# Cell_Monitor_V0_1.net
KiCad netlist of a schematic drawn in Altium Designer
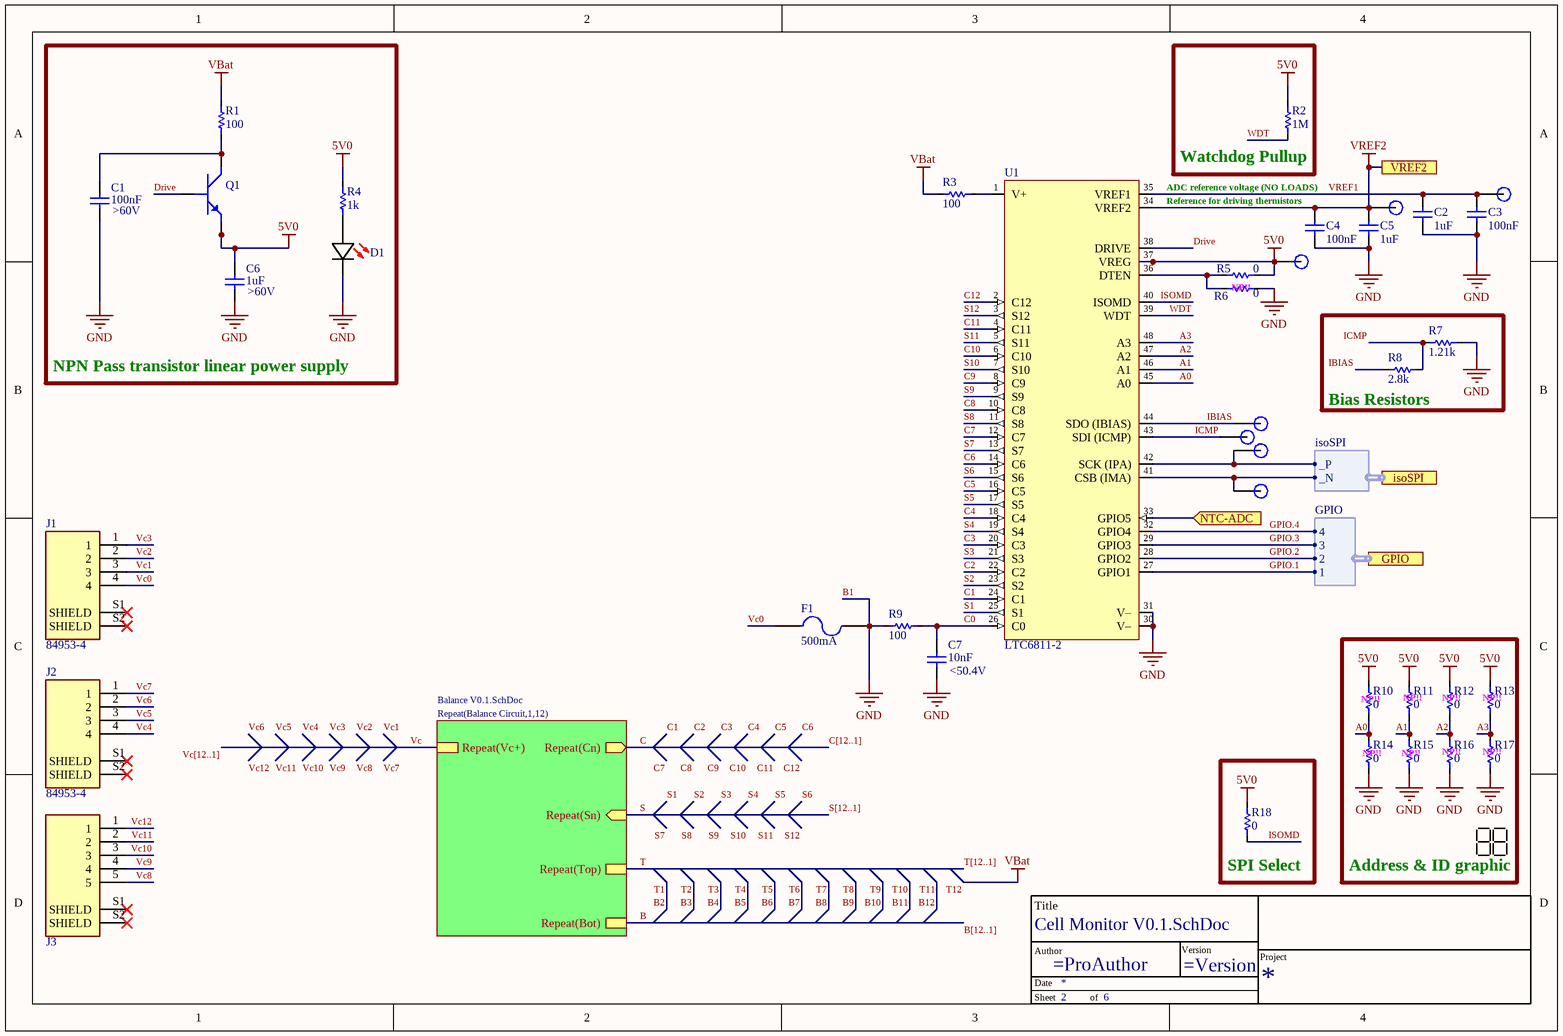
[diagram p0: Cell Monitor V0.1.SchDoc]

(export (version "E")
  (design (tool "Eeschema 10.0.6"))
  (components
    (comp (ref "*") (value "TitleBlock") (libsource (lib "SchematicLib") (part "TitleBlock")))
    (comp (ref "C1")
      (value "100nF")
      (footprint "C_0603")
      (description "Capacitor")
      (fields (field (name "VOLTAGE") ">60V") (field (name "Comment") "C"))
      (libsource (lib "Passives") (part "Capacitor"))
    )
    (comp (ref "C2")
      (value "1uF")
      (footprint "C-0402")
      (description "Capacitor")
      (fields (field (name "Comment") "C"))
      (libsource (lib "Passives") (part "Capacitor"))
    )
    (comp (ref "C3")
      (value "100nF")
      (footprint "C-0402")
      (description "Capacitor")
      (fields (field (name "Comment") "C"))
      (libsource (lib "Passives") (part "Capacitor"))
    )
    (comp (ref "C4")
      (value "100nF")
      (footprint "C-0402")
      (description "Capacitor")
      (fields (field (name "Comment") "C"))
      (libsource (lib "Passives") (part "Capacitor"))
    )
    (comp (ref "C5")
      (value "1uF")
      (footprint "C-0402")
      (description "Capacitor")
      (fields (field (name "Comment") "C"))
      (libsource (lib "Passives") (part "Capacitor"))
    )
    (comp (ref "C6")
      (value "1uF")
      (footprint "C_0603")
      (description "Capacitor")
      (fields (field (name "VOLTAGE") ">60V") (field (name "Comment") "C"))
      (libsource (lib "Passives") (part "Capacitor"))
    )
    (comp (ref "C7")
      (value "10nF")
      (footprint "C_0603")
      (description "Capacitor")
      (fields (field (name "VOLTAGE") "<50.4V") (field (name "Comment") "C"))
      (libsource (lib "Passives") (part "Capacitor"))
    )
    (comp (ref "D1")
      (value "150060SS55040")
      (footprint "LED (0603)")
      (description "LED RED DIFFUSED 0603 SMD")
      (fields (field (name "MANUFACTURER") "Wurth Electronics"))
      (libsource (lib "LEDLib") (part "150060SS55040"))
    )
    (comp (ref "F1")
      (value "0466.500NR")
      (footprint "0466.500NR")
      (fields
        (field (name "MANUFACTURER") "Littelfuse")
        (field (name "CURRENT RATING") "500mA")
        (field (name "PUBLISHER") "Altium Limited")
      )
      (libsource (lib "Miscellaneous Devices") (part "Fuse 2"))
    )
    (comp (ref "J1")
      (value "84953-4")
      (footprint "84953-4")
      (fields (field (name "MF") "{'manufacturer': u'TE Connectivity'}"))
      (libsource (lib "TE_Con") (part "84953-4"))
    )
    (comp (ref "J2")
      (value "84953-4")
      (footprint "84953-4")
      (fields (field (name "MF") "{'manufacturer': u'TE Connectivity'}"))
      (libsource (lib "TE_Con") (part "84953-4"))
    )
    (comp (ref "J3") (value "84953-5") (footprint "84953-5") (libsource (lib "TE_Con") (part "84953-5")))
    (comp (ref "NT1") (value "NetTie") (footprint "NetTie") (libsource (lib "SchematicLib") (part "NetTie")))
    (comp (ref "NT2") (value "NetTie") (footprint "NetTie") (libsource (lib "SchematicLib") (part "NetTie")))
    (comp (ref "Q1")
      (value "PHPT60603NYX")
      (footprint "LFPAK56 (SOT669)")
      (description "60V, 3 A NPN high power bipolar transistor")
      (libsource (lib "SchematicLib") (part "PHPT60603NYX"))
    )
    (comp (ref "R1")
      (value "100")
      (footprint "R_2010")
      (description "Resistor")
      (libsource (lib "Passives") (part "Resistor"))
    )
    (comp (ref "R2")
      (value "1M")
      (footprint "R_0402")
      (description "Resistor")
      (libsource (lib "Passives") (part "Resistor"))
    )
    (comp (ref "R3")
      (value "100")
      (footprint "R_2010")
      (description "Resistor")
      (libsource (lib "Passives") (part "Resistor"))
    )
    (comp (ref "R4")
      (value "1k")
      (footprint "R-0603")
      (description "Resistor")
      (libsource (lib "Passives") (part "Resistor"))
    )
    (comp (ref "R5")
      (value "0")
      (footprint "R_0402")
      (description "Resistor")
      (libsource (lib "Passives") (part "Resistor"))
    )
    (comp (ref "R6")
      (value "0")
      (footprint "R_0402")
      (description "Resistor")
      (libsource (lib "Passives") (part "Resistor"))
    )
    (comp (ref "R7")
      (value "1.21k")
      (footprint "R_0402")
      (description "Resistor")
      (libsource (lib "Passives") (part "Resistor"))
    )
    (comp (ref "R8")
      (value "2.8k")
      (footprint "R_0402")
      (description "Resistor")
      (libsource (lib "Passives") (part "Resistor"))
    )
    (comp (ref "R9")
      (value "100")
      (footprint "R-0603")
      (description "Resistor")
      (libsource (lib "Passives") (part "Resistor"))
    )
    (comp (ref "R10")
      (value "0")
      (footprint "R_0402")
      (description "Resistor")
      (libsource (lib "Passives") (part "Resistor"))
    )
    (comp (ref "R11")
      (value "0")
      (footprint "R_0402")
      (description "Resistor")
      (libsource (lib "Passives") (part "Resistor"))
    )
    (comp (ref "R12")
      (value "0")
      (footprint "R_0402")
      (description "Resistor")
      (libsource (lib "Passives") (part "Resistor"))
    )
    (comp (ref "R13")
      (value "0")
      (footprint "R_0402")
      (description "Resistor")
      (libsource (lib "Passives") (part "Resistor"))
    )
    (comp (ref "R14")
      (value "0")
      (footprint "R_0402")
      (description "Resistor")
      (libsource (lib "Passives") (part "Resistor"))
    )
    (comp (ref "R15")
      (value "0")
      (footprint "R_0402")
      (description "Resistor")
      (libsource (lib "Passives") (part "Resistor"))
    )
    (comp (ref "R16")
      (value "0")
      (footprint "R_0402")
      (description "Resistor")
      (libsource (lib "Passives") (part "Resistor"))
    )
    (comp (ref "R17")
      (value "0")
      (footprint "R_0402")
      (description "Resistor")
      (libsource (lib "Passives") (part "Resistor"))
    )
    (comp (ref "R18")
      (value "0")
      (footprint "R_0402")
      (description "Resistor")
      (libsource (lib "Passives") (part "Resistor"))
    )
    (comp (ref "S1")
      (value "2x7Segment")
      (footprint "2x7Segment")
      (libsource (lib "SchematicLib") (part "2x7Segment"))
    )
    (comp (ref "TP1")
      (value "VREF1")
      (footprint "Test Point")
      (description "1.2mm Test point")
      (libsource (lib "SchematicLib") (part "Test Point"))
    )
    (comp (ref "TP2")
      (value "VREF2")
      (footprint "Test Point")
      (description "1.2mm Test point")
      (libsource (lib "SchematicLib") (part "Test Point"))
    )
    (comp (ref "TP3")
      (value "5V0")
      (footprint "Test Point")
      (description "1.2mm Test point")
      (libsource (lib "SchematicLib") (part "Test Point"))
    )
    (comp (ref "TP4")
      (value "IBIAS")
      (footprint "Test Point")
      (description "1.2mm Test point")
      (libsource (lib "SchematicLib") (part "Test Point"))
    )
    (comp (ref "TP5")
      (value "ICMP")
      (footprint "Test Point")
      (description "1.2mm Test point")
      (libsource (lib "SchematicLib") (part "Test Point"))
    )
    (comp (ref "TP6")
      (value "IPA")
      (footprint "Test Point")
      (description "1.2mm Test point")
      (libsource (lib "SchematicLib") (part "Test Point"))
    )
    (comp (ref "TP7")
      (value "IMA")
      (footprint "Test Point")
      (description "1.2mm Test point")
      (libsource (lib "SchematicLib") (part "Test Point"))
    )
    (comp (ref "U1")
      (value "LTC6811-2")
      (footprint "SSOP50P780X200-48N")
      (description "12 Channel Multicell Battery Monitor with Addressable Interface")
      (libsource (lib "SchematicLib") (part "LTC6811-2"))
    )
  )
  (nets
    (net (code "3") (name "/A0") (class "Default")
      (node (ref "R10") (pin "1") (pinfunction "1_1") (pintype "passive"))
      (node (ref "R14") (pin "2") (pinfunction "2_2") (pintype "passive"))
      (node (ref "U1") (pin "45") (pinfunction "A0_45") (pintype "passive"))
    )
    (net (code "4") (name "/A1") (class "Default")
      (node (ref "R11") (pin "1") (pinfunction "1_1") (pintype "passive"))
      (node (ref "R15") (pin "2") (pinfunction "2_2") (pintype "passive"))
      (node (ref "U1") (pin "46") (pinfunction "A1_46") (pintype "passive"))
    )
    (net (code "5") (name "/A2") (class "Default")
      (node (ref "R12") (pin "1") (pinfunction "1_1") (pintype "passive"))
      (node (ref "R16") (pin "2") (pinfunction "2_2") (pintype "passive"))
      (node (ref "U1") (pin "47") (pinfunction "A2_47") (pintype "passive"))
    )
    (net (code "6") (name "/A3") (class "Default")
      (node (ref "R13") (pin "1") (pinfunction "1_1") (pintype "passive"))
      (node (ref "R17") (pin "2") (pinfunction "2_2") (pintype "passive"))
      (node (ref "U1") (pin "48") (pinfunction "A3_48") (pintype "passive"))
    )
    (net (code "8") (name "/B1") (class "Default") (node (ref "NT1") (pin "2") (pintype "passive")))
    (net (code "11") (name "/C0") (class "Default")
      (node (ref "C7") (pin "2") (pinfunction "2_2") (pintype "passive"))
      (node (ref "R9") (pin "2") (pinfunction "2_2") (pintype "passive"))
      (node (ref "U1") (pin "26") (pinfunction "C0_26") (pintype "input"))
    )
    (net (code "12") (name "/C1") (class "Default")
      (node (ref "U1") (pin "24") (pinfunction "C1_24") (pintype "input"))
    )
    (net (code "13") (name "/C2") (class "Default")
      (node (ref "U1") (pin "22") (pinfunction "C2_22") (pintype "input"))
    )
    (net (code "14") (name "/C3") (class "Default")
      (node (ref "U1") (pin "20") (pinfunction "C3_20") (pintype "input"))
    )
    (net (code "15") (name "/C4") (class "Default")
      (node (ref "U1") (pin "18") (pinfunction "C4_18") (pintype "input"))
    )
    (net (code "16") (name "/C5") (class "Default")
      (node (ref "U1") (pin "16") (pinfunction "C5_16") (pintype "input"))
    )
    (net (code "17") (name "/C6") (class "Default")
      (node (ref "U1") (pin "14") (pinfunction "C6_14") (pintype "input"))
    )
    (net (code "18") (name "/C7") (class "Default")
      (node (ref "U1") (pin "12") (pinfunction "C7_12") (pintype "input"))
    )
    (net (code "19") (name "/C8") (class "Default")
      (node (ref "U1") (pin "10") (pinfunction "C8_10") (pintype "input"))
    )
    (net (code "20") (name "/C9") (class "Default")
      (node (ref "U1") (pin "8") (pinfunction "C9_8") (pintype "input"))
    )
    (net (code "21") (name "/C10") (class "Default")
      (node (ref "U1") (pin "6") (pinfunction "C10_6") (pintype "input"))
    )
    (net (code "22") (name "/C11") (class "Default")
      (node (ref "U1") (pin "4") (pinfunction "C11_4") (pintype "input"))
    )
    (net (code "23") (name "/C12") (class "Default")
      (node (ref "U1") (pin "2") (pinfunction "C12_2") (pintype "input"))
    )
    (net (code "25") (name "/Drive") (class "Default")
      (node (ref "Q1") (pin "4") (pinfunction "Base_4") (pintype "passive"))
      (node (ref "U1") (pin "38") (pinfunction "DRIVE_38") (pintype "passive"))
    )
    (net (code "26") (name "/GPIO.1") (class "Default")
      (node (ref "U1") (pin "27") (pinfunction "GPIO1_27") (pintype "bidirectional"))
    )
    (net (code "27") (name "/GPIO.2") (class "Default")
      (node (ref "U1") (pin "28") (pinfunction "GPIO2_28") (pintype "bidirectional"))
    )
    (net (code "28") (name "/GPIO.3") (class "Default")
      (node (ref "U1") (pin "29") (pinfunction "GPIO3_29") (pintype "bidirectional"))
    )
    (net (code "29") (name "/GPIO.4") (class "Default")
      (node (ref "U1") (pin "32") (pinfunction "GPIO4_32") (pintype "bidirectional"))
    )
    (net (code "30") (name "/IBIAS") (class "Default")
      (node (ref "R8") (pin "1") (pinfunction "1_1") (pintype "passive"))
      (node (ref "TP4") (pin "1") (pinfunction "1_1") (pintype "passive"))
      (node (ref "U1") (pin "44") (pinfunction "SDO_(IBIAS)_44") (pintype "passive"))
    )
    (net (code "31") (name "/ICMP") (class "Default")
      (node (ref "R7") (pin "1") (pinfunction "1_1") (pintype "passive"))
      (node (ref "R8") (pin "2") (pinfunction "2_2") (pintype "passive"))
      (node (ref "TP5") (pin "1") (pinfunction "1_1") (pintype "passive"))
      (node (ref "U1") (pin "43") (pinfunction "SDI_(ICMP)_43") (pintype "passive"))
    )
    (net (code "32") (name "/ISOMD") (class "Default")
      (node (ref "R18") (pin "1") (pinfunction "1_1") (pintype "passive"))
      (node (ref "U1") (pin "40") (pinfunction "ISOMD_40") (pintype "passive"))
    )
    (net (code "33") (name "/NTC-ADC") (class "Default")
      (node (ref "U1") (pin "33") (pinfunction "GPIO5_33") (pintype "input"))
    )
    (net (code "35") (name "/S1") (class "Default")
      (node (ref "U1") (pin "25") (pinfunction "S1_25") (pintype "output"))
    )
    (net (code "36") (name "/S2") (class "Default")
      (node (ref "U1") (pin "23") (pinfunction "S2_23") (pintype "output"))
    )
    (net (code "37") (name "/S3") (class "Default")
      (node (ref "U1") (pin "21") (pinfunction "S3_21") (pintype "output"))
    )
    (net (code "38") (name "/S4") (class "Default")
      (node (ref "U1") (pin "19") (pinfunction "S4_19") (pintype "output"))
    )
    (net (code "39") (name "/S5") (class "Default")
      (node (ref "U1") (pin "17") (pinfunction "S5_17") (pintype "output"))
    )
    (net (code "40") (name "/S6") (class "Default")
      (node (ref "U1") (pin "15") (pinfunction "S6_15") (pintype "output"))
    )
    (net (code "41") (name "/S7") (class "Default")
      (node (ref "U1") (pin "13") (pinfunction "S7_13") (pintype "output"))
    )
    (net (code "42") (name "/S8") (class "Default")
      (node (ref "U1") (pin "11") (pinfunction "S8_11") (pintype "output"))
    )
    (net (code "43") (name "/S9") (class "Default")
      (node (ref "U1") (pin "9") (pinfunction "S9_9") (pintype "output"))
    )
    (net (code "44") (name "/S10") (class "Default")
      (node (ref "U1") (pin "7") (pinfunction "S10_7") (pintype "output"))
    )
    (net (code "45") (name "/S11") (class "Default")
      (node (ref "U1") (pin "5") (pinfunction "S11_5") (pintype "output"))
    )
    (net (code "46") (name "/S12") (class "Default")
      (node (ref "U1") (pin "3") (pinfunction "S12_3") (pintype "output"))
    )
    (net (code "60") (name "/T12") (class "Default") (node (ref "NT2") (pin "1") (pintype "passive")))
    (net (code "62") (name "/VREF1") (class "Default")
      (node (ref "C2") (pin "2") (pinfunction "2_2") (pintype "passive"))
      (node (ref "C3") (pin "2") (pinfunction "2_2") (pintype "passive"))
      (node (ref "TP1") (pin "1") (pinfunction "1_1") (pintype "passive"))
      (node (ref "U1") (pin "35") (pinfunction "VREF1_35") (pintype "power_in"))
    )
    (net (code "64") (name "/Vc0") (class "Default")
      (node (ref "F1") (pin "1") (pinfunction "1_1") (pintype "passive"))
      (node (ref "J1") (pin "4") (pinfunction "4_4") (pintype "passive"))
    )
    (net (code "65") (name "/Vc1") (class "Default")
      (node (ref "J1") (pin "3") (pinfunction "3_3") (pintype "passive"))
    )
    (net (code "66") (name "/Vc2") (class "Default")
      (node (ref "J1") (pin "2") (pinfunction "2_2") (pintype "passive"))
    )
    (net (code "67") (name "/Vc3") (class "Default")
      (node (ref "J1") (pin "1") (pinfunction "1_1") (pintype "passive"))
    )
    (net (code "68") (name "/Vc4") (class "Default")
      (node (ref "J2") (pin "4") (pinfunction "4_4") (pintype "passive"))
    )
    (net (code "69") (name "/Vc5") (class "Default")
      (node (ref "J2") (pin "3") (pinfunction "3_3") (pintype "passive"))
    )
    (net (code "70") (name "/Vc6") (class "Default")
      (node (ref "J2") (pin "2") (pinfunction "2_2") (pintype "passive"))
    )
    (net (code "71") (name "/Vc7") (class "Default")
      (node (ref "J2") (pin "1") (pinfunction "1_1") (pintype "passive"))
    )
    (net (code "72") (name "/Vc8") (class "Default")
      (node (ref "J3") (pin "5") (pinfunction "5_5") (pintype "passive"))
    )
    (net (code "73") (name "/Vc9") (class "Default")
      (node (ref "J3") (pin "4") (pinfunction "4_4") (pintype "passive"))
    )
    (net (code "74") (name "/Vc10") (class "Default")
      (node (ref "J3") (pin "3") (pinfunction "3_3") (pintype "passive"))
    )
    (net (code "75") (name "/Vc11") (class "Default")
      (node (ref "J3") (pin "2") (pinfunction "2_2") (pintype "passive"))
    )
    (net (code "76") (name "/Vc12") (class "Default")
      (node (ref "J3") (pin "1") (pinfunction "1_1") (pintype "passive"))
    )
    (net (code "78") (name "/WDT") (class "Default")
      (node (ref "R2") (pin "1") (pinfunction "1_1") (pintype "passive"))
      (node (ref "U1") (pin "39") (pinfunction "WDT_39") (pintype "passive"))
    )
    (net (code "81") (name "5V0") (class "Default")
      (node (ref "C6") (pin "2") (pinfunction "2_2") (pintype "passive"))
      (node (ref "Q1") (pin "1") (pinfunction "Emitter_1") (pintype "passive"))
      (node (ref "Q1") (pin "2") (pinfunction "Emitter_2") (pintype "passive"))
      (node (ref "Q1") (pin "3") (pinfunction "Emitter_3") (pintype "passive"))
      (node (ref "R10") (pin "2") (pinfunction "2_2") (pintype "passive"))
      (node (ref "R11") (pin "2") (pinfunction "2_2") (pintype "passive"))
      (node (ref "R12") (pin "2") (pinfunction "2_2") (pintype "passive"))
      (node (ref "R13") (pin "2") (pinfunction "2_2") (pintype "passive"))
      (node (ref "R18") (pin "2") (pinfunction "2_2") (pintype "passive"))
      (node (ref "R2") (pin "2") (pinfunction "2_2") (pintype "passive"))
      (node (ref "R4") (pin "2") (pinfunction "2_2") (pintype "passive"))
      (node (ref "R5") (pin "2") (pinfunction "2_2") (pintype "passive"))
      (node (ref "TP3") (pin "1") (pinfunction "1_1") (pintype "passive"))
      (node (ref "U1") (pin "37") (pinfunction "VREG_37") (pintype "power_in"))
    )
    (net (code "82") (name "GND") (class "Default")
      (node (ref "C1") (pin "1") (pinfunction "1_1") (pintype "passive"))
      (node (ref "C2") (pin "1") (pinfunction "1_1") (pintype "passive"))
      (node (ref "C3") (pin "1") (pinfunction "1_1") (pintype "passive"))
      (node (ref "C4") (pin "1") (pinfunction "1_1") (pintype "passive"))
      (node (ref "C5") (pin "1") (pinfunction "1_1") (pintype "passive"))
      (node (ref "C6") (pin "1") (pinfunction "1_1") (pintype "passive"))
      (node (ref "C7") (pin "1") (pinfunction "1_1") (pintype "passive"))
      (node (ref "D1") (pin "1") (pinfunction "K_1") (pintype "passive"))
      (node (ref "F1") (pin "2") (pinfunction "2_2") (pintype "passive"))
      (node (ref "NT1") (pin "1") (pintype "passive"))
      (node (ref "R14") (pin "1") (pinfunction "1_1") (pintype "passive"))
      (node (ref "R15") (pin "1") (pinfunction "1_1") (pintype "passive"))
      (node (ref "R16") (pin "1") (pinfunction "1_1") (pintype "passive"))
      (node (ref "R17") (pin "1") (pinfunction "1_1") (pintype "passive"))
      (node (ref "R6") (pin "1") (pinfunction "1_1") (pintype "passive"))
      (node (ref "R7") (pin "2") (pinfunction "2_2") (pintype "passive"))
      (node (ref "R9") (pin "1") (pinfunction "1_1") (pintype "passive"))
      (node (ref "U1") (pin "30") (pinfunction "V–_30") (pintype "power_in"))
      (node (ref "U1") (pin "31") (pinfunction "V–_31") (pintype "power_in"))
    )
    (net (code "83") (name "Net-(D1-A)") (class "Default")
      (node (ref "D1") (pin "2") (pinfunction "A_2") (pintype "passive"))
      (node (ref "R4") (pin "1") (pinfunction "1_1") (pintype "passive"))
    )
    (net (code "84") (name "Net-(Q1-Collector)") (class "Default")
      (node (ref "C1") (pin "2") (pinfunction "2_2") (pintype "passive"))
      (node (ref "Q1") (pin "5") (pinfunction "Collector_5") (pintype "passive"))
      (node (ref "R1") (pin "1") (pinfunction "1_1") (pintype "passive"))
    )
    (net (code "85") (name "Net-(U1-CSB_(IMA))") (class "Default")
      (node (ref "TP7") (pin "1") (pinfunction "1_1") (pintype "passive"))
      (node (ref "U1") (pin "41") (pinfunction "CSB_(IMA)_41") (pintype "bidirectional"))
    )
    (net (code "86") (name "Net-(U1-DTEN)") (class "Default")
      (node (ref "R5") (pin "1") (pinfunction "1_1") (pintype "passive"))
      (node (ref "R6") (pin "2") (pinfunction "2_2") (pintype "passive"))
      (node (ref "U1") (pin "36") (pinfunction "DTEN_36") (pintype "passive"))
    )
    (net (code "87") (name "Net-(U1-SCK_(IPA))") (class "Default")
      (node (ref "TP6") (pin "1") (pinfunction "1_1") (pintype "passive"))
      (node (ref "U1") (pin "42") (pinfunction "SCK_(IPA)_42") (pintype "bidirectional"))
    )
    (net (code "88") (name "Net-(U1-V+)") (class "Default")
      (node (ref "R3") (pin "1") (pinfunction "1_1") (pintype "passive"))
      (node (ref "U1") (pin "1") (pinfunction "V+_1") (pintype "power_in"))
    )
    (net (code "89") (name "VBat") (class "Default")
      (node (ref "NT2") (pin "2") (pintype "passive"))
      (node (ref "R1") (pin "2") (pinfunction "2_2") (pintype "passive"))
      (node (ref "R3") (pin "2") (pinfunction "2_2") (pintype "passive"))
    )
    (net (code "90") (name "VREF2") (class "Default")
      (node (ref "C4") (pin "2") (pinfunction "2_2") (pintype "passive"))
      (node (ref "C5") (pin "2") (pinfunction "2_2") (pintype "passive"))
      (node (ref "TP2") (pin "1") (pinfunction "1_1") (pintype "passive"))
      (node (ref "U1") (pin "34") (pinfunction "VREF2_34") (pintype "power_in"))
    )
    (net (code "91") (name "unconnected-(J1-SHIELD-PadS1)") (class "Default")
      (node (ref "J1") (pin "S1") (pinfunction "SHIELD_S1") (pintype "passive+no_connect"))
    )
    (net (code "92") (name "unconnected-(J1-SHIELD-PadS2)") (class "Default")
      (node (ref "J1") (pin "S2") (pinfunction "SHIELD_S2") (pintype "passive+no_connect"))
    )
    (net (code "93") (name "unconnected-(J2-SHIELD-PadS1)") (class "Default")
      (node (ref "J2") (pin "S1") (pinfunction "SHIELD_S1") (pintype "passive+no_connect"))
    )
    (net (code "94") (name "unconnected-(J2-SHIELD-PadS2)") (class "Default")
      (node (ref "J2") (pin "S2") (pinfunction "SHIELD_S2") (pintype "passive+no_connect"))
    )
    (net (code "95") (name "unconnected-(J3-SHIELD-PadS1)") (class "Default")
      (node (ref "J3") (pin "S1") (pinfunction "SHIELD_S1") (pintype "passive+no_connect"))
    )
    (net (code "96") (name "unconnected-(J3-SHIELD-PadS2)") (class "Default")
      (node (ref "J3") (pin "S2") (pinfunction "SHIELD_S2") (pintype "passive+no_connect"))
    )
  )
)
